# SIT1533_Oscillator.net
KiCad netlist of a schematic drawn in Altium Designer
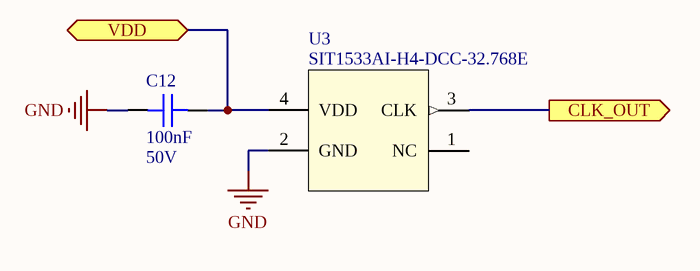
[diagram p0: SIT1533_Oscillator.SchDoc]

(export (version "E")
  (design (tool "Eeschema 10.0.6"))
  (components
    (comp (ref "C12")
      (value "CAP CER 0.1UF 50V X7R 0402")
      (footprint "C0402")
      (description "0.1µF ±10% 50V Ceramic Capacitor X7R 0402 (1005 Metric)")
      (fields
        (field (name "MANUFACTURER") "TDK")
        (field (name "MANUFACTURER PART NUMBER") "CGA2B3X7R1H104K050BB")
        (field (name "CAPACITANCE") "100nF")
        (field (name "VOLTAGE") "50V")
      )
      (libsource (lib "capacitors_smd") (part "CAP CER 0.1UF 50V X7R 0402"))
    )
    (comp (ref "U3")
      (value "IC SIT1533AI-H4-DCC-32.768E MEMS OSC XO 32.7680KHZ LVCMOS")
      (footprint "XTAL4_SiT1533_SIT")
      (description "32.768kHz XO (Standard) LVCMOS Oscillator 1.5V ~ 3.63V  4-SMD, No Lead")
      (fields
        (field (name "MANUFACTURER") "SiTime")
        (field (name "MANUFACTURER PART NUMBER") "SIT1533AI-H4-DCC-32.768E")
      )
      (libsource (lib "BLDC_Motor_Driver") (part "IC SIT1533AI-H4-DCC-32.768E MEMS OSC XO 32.7680KHZ LVCMOS"))
    )
  )
  (nets
    (net (code "1") (name "/CLK_OUT") (class "Default")
      (node (ref "U3") (pin "3") (pinfunction "CLK_3") (pintype "output"))
    )
    (net (code "2") (name "/VDD") (class "Default")
      (node (ref "C12") (pin "2") (pinfunction "2_2") (pintype "passive"))
      (node (ref "U3") (pin "4") (pinfunction "VDD_4") (pintype "power_in"))
    )
    (net (code "3") (name "GND") (class "Default")
      (node (ref "C12") (pin "1") (pinfunction "1_1") (pintype "passive"))
      (node (ref "U3") (pin "2") (pinfunction "GND_2") (pintype "power_in"))
    )
    (net (code "4") (name "unconnected-(U3-NC-Pad1)") (class "Default")
      (node (ref "U3") (pin "1") (pinfunction "NC_1") (pintype "passive"))
    )
  )
)
